# LED.net
KiCad netlist of a schematic drawn in Altium Designer
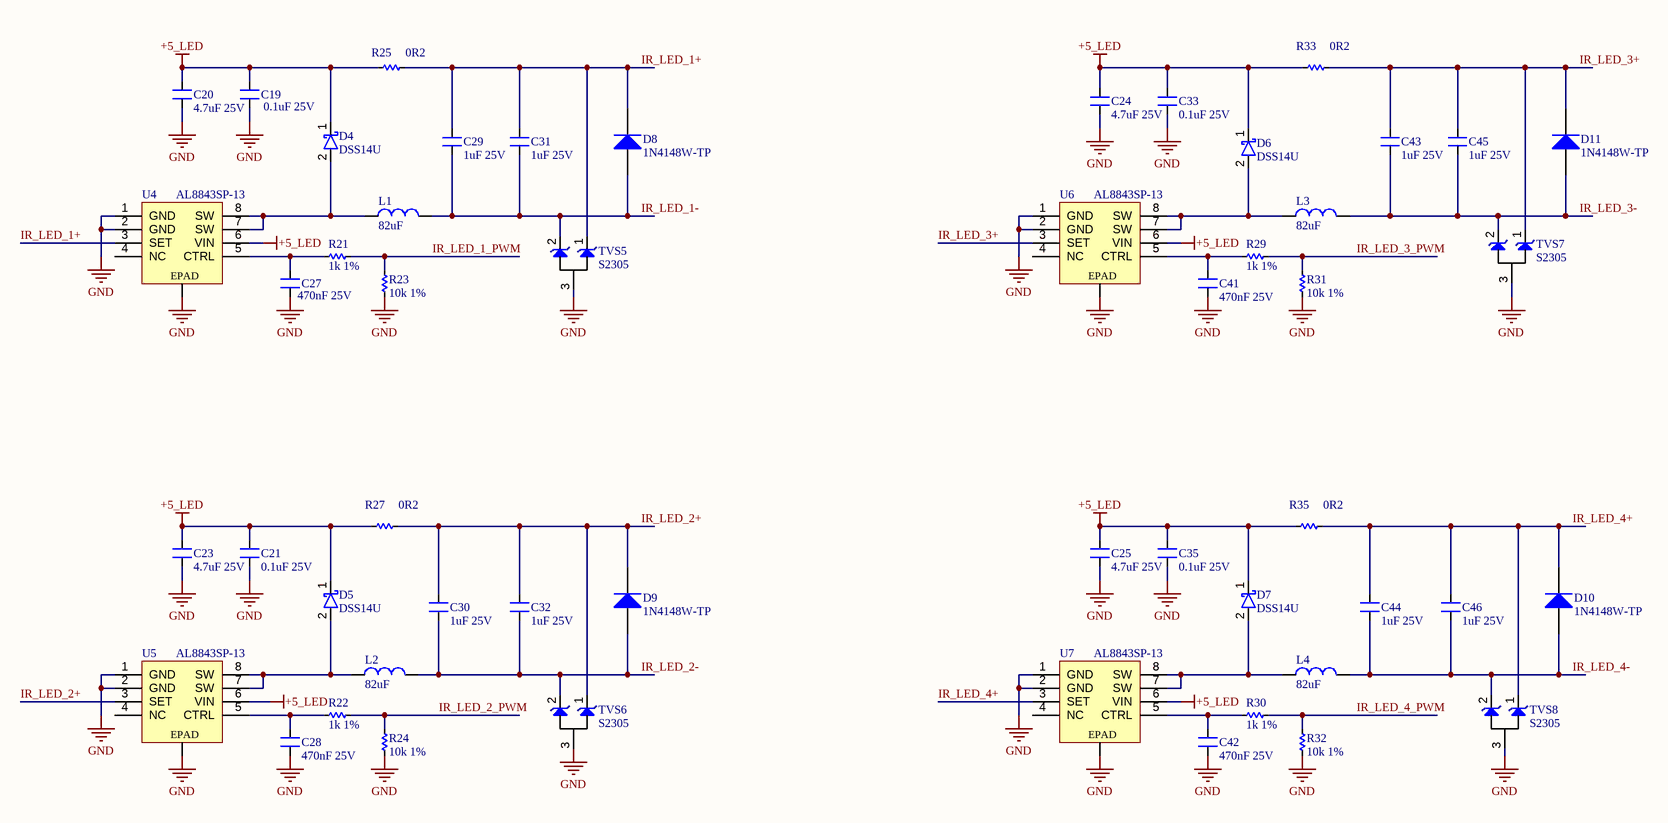
[diagram p0: LED.SchDoc]

(export (version "E")
  (design (tool "Eeschema 10.0.6"))
  (components
    (comp (ref "C19")
      (value "0.1uF 25V")
      (footprint "CN-SMD-0603")
      (libsource (lib "Sang_library") (part "Capacitors"))
    )
    (comp (ref "C20")
      (value "4.7uF 25V")
      (footprint "CN-SMD-0603")
      (libsource (lib "Sang_library") (part "Capacitors"))
    )
    (comp (ref "C21")
      (value "0.1uF 25V")
      (footprint "CN-SMD-0603")
      (libsource (lib "Sang_library") (part "Capacitors"))
    )
    (comp (ref "C23")
      (value "4.7uF 25V")
      (footprint "CN-SMD-0603")
      (libsource (lib "Sang_library") (part "Capacitors"))
    )
    (comp (ref "C24")
      (value "4.7uF 25V")
      (footprint "CN-SMD-0603")
      (libsource (lib "Sang_library") (part "Capacitors"))
    )
    (comp (ref "C25")
      (value "4.7uF 25V")
      (footprint "CN-SMD-0603")
      (libsource (lib "Sang_library") (part "Capacitors"))
    )
    (comp (ref "C27")
      (value "470nF 25V")
      (footprint "CN-SMD-0603")
      (libsource (lib "Sang_library") (part "Capacitors"))
    )
    (comp (ref "C28")
      (value "470nF 25V")
      (footprint "CN-SMD-0603")
      (libsource (lib "Sang_library") (part "Capacitors"))
    )
    (comp (ref "C29")
      (value "1uF 25V")
      (footprint "CN-SMD-0603")
      (libsource (lib "Sang_library") (part "Capacitors"))
    )
    (comp (ref "C30")
      (value "1uF 25V")
      (footprint "CN-SMD-0603")
      (libsource (lib "Sang_library") (part "Capacitors"))
    )
    (comp (ref "C31")
      (value "1uF 25V")
      (footprint "CN-SMD-0603")
      (libsource (lib "Sang_library") (part "Capacitors"))
    )
    (comp (ref "C32")
      (value "1uF 25V")
      (footprint "CN-SMD-0603")
      (libsource (lib "Sang_library") (part "Capacitors"))
    )
    (comp (ref "C33")
      (value "0.1uF 25V")
      (footprint "CN-SMD-0603")
      (libsource (lib "Sang_library") (part "Capacitors"))
    )
    (comp (ref "C35")
      (value "0.1uF 25V")
      (footprint "CN-SMD-0603")
      (libsource (lib "Sang_library") (part "Capacitors"))
    )
    (comp (ref "C41")
      (value "470nF 25V")
      (footprint "CN-SMD-0603")
      (libsource (lib "Sang_library") (part "Capacitors"))
    )
    (comp (ref "C42")
      (value "470nF 25V")
      (footprint "CN-SMD-0603")
      (libsource (lib "Sang_library") (part "Capacitors"))
    )
    (comp (ref "C43")
      (value "1uF 25V")
      (footprint "CN-SMD-0603")
      (libsource (lib "Sang_library") (part "Capacitors"))
    )
    (comp (ref "C44")
      (value "1uF 25V")
      (footprint "CN-SMD-0603")
      (libsource (lib "Sang_library") (part "Capacitors"))
    )
    (comp (ref "C45")
      (value "1uF 25V")
      (footprint "CN-SMD-0603")
      (libsource (lib "Sang_library") (part "Capacitors"))
    )
    (comp (ref "C46")
      (value "1uF 25V")
      (footprint "CN-SMD-0603")
      (libsource (lib "Sang_library") (part "Capacitors"))
    )
    (comp (ref "D4") (value "DSS14U") (footprint "sod-123") (libsource (lib "Sang_library") (part "DSS14U")))
    (comp (ref "D5") (value "DSS14U") (footprint "sod-123") (libsource (lib "Sang_library") (part "DSS14U")))
    (comp (ref "D6") (value "DSS14U") (footprint "sod-123") (libsource (lib "Sang_library") (part "DSS14U")))
    (comp (ref "D7") (value "DSS14U") (footprint "sod-123") (libsource (lib "Sang_library") (part "DSS14U")))
    (comp (ref "D8")
      (value "1N4148W-TP")
      (footprint "SOD-123")
      (description "DIODE GEN PURP 100V 300MA SOD123")
      (fields (field (name "MPN") "1N4148W-7-F") (field (name "MFR") "Diodes Incorporated"))
      (libsource (lib "Sang_library") (part "1N4148-W-7"))
    )
    (comp (ref "D9")
      (value "1N4148W-TP")
      (footprint "SOD-123")
      (description "DIODE GEN PURP 100V 300MA SOD123")
      (fields (field (name "MPN") "1N4148W-7-F") (field (name "MFR") "Diodes Incorporated"))
      (libsource (lib "Sang_library") (part "1N4148-W-7"))
    )
    (comp (ref "D10")
      (value "1N4148W-TP")
      (footprint "SOD-123")
      (description "DIODE GEN PURP 100V 300MA SOD123")
      (fields (field (name "MPN") "1N4148W-7-F") (field (name "MFR") "Diodes Incorporated"))
      (libsource (lib "Sang_library") (part "1N4148-W-7"))
    )
    (comp (ref "D11")
      (value "1N4148W-TP")
      (footprint "SOD-123")
      (description "DIODE GEN PURP 100V 300MA SOD123")
      (fields (field (name "MPN") "1N4148W-7-F") (field (name "MFR") "Diodes Incorporated"))
      (libsource (lib "Sang_library") (part "1N4148-W-7"))
    )
    (comp (ref "L1")
      (value "82uF")
      (footprint "L-SMD-M-4.8x4.8x2.8mm")
      (description "FIXED IND 82UH 2.25A 160MOHM SMD\r\nPN: 744770182")
      (fields
        (field (name "PARTNO") "78477010")
        (field (name "MANUFACTURER") "Wurth Elektronik")
        (field (name "CREATED BY") "Baojun Chen")
      )
      (libsource (lib "Sang_library") (part "L-SMD-1"))
    )
    (comp (ref "L2")
      (value "82uF")
      (footprint "L-SMD-M-4.8x4.8x2.8mm")
      (description "FIXED IND 82UH 2.25A 160MOHM SMD\r\nPN: 744770182")
      (fields
        (field (name "PARTNO") "78477010")
        (field (name "MANUFACTURER") "Wurth Elektronik")
        (field (name "CREATED BY") "Baojun Chen")
      )
      (libsource (lib "Sang_library") (part "L-SMD-1"))
    )
    (comp (ref "L3")
      (value "82uF")
      (footprint "L-SMD-M-4.8x4.8x2.8mm")
      (description "FIXED IND 82UH 2.25A 160MOHM SMD\r\nPN: 744770182")
      (fields
        (field (name "PARTNO") "78477010")
        (field (name "MANUFACTURER") "Wurth Elektronik")
        (field (name "CREATED BY") "Baojun Chen")
      )
      (libsource (lib "Sang_library") (part "L-SMD-1"))
    )
    (comp (ref "L4")
      (value "82uF")
      (footprint "L-SMD-M-4.8x4.8x2.8mm")
      (description "FIXED IND 82UH 2.25A 160MOHM SMD\r\nPN: 744770182")
      (fields
        (field (name "PARTNO") "78477010")
        (field (name "MANUFACTURER") "Wurth Elektronik")
        (field (name "CREATED BY") "Baojun Chen")
      )
      (libsource (lib "Sang_library") (part "L-SMD-1"))
    )
    (comp (ref "R21")
      (value "1k 1%")
      (footprint "RES-SMD-0603")
      (description "SMD")
      (fields
        (field (name "MANUFACTURER") "Generic Components")
        (field (name "PUBLISHER") "Altium Hobart Technology Centre")
      )
      (libsource (lib "Sang_library") (part "Res SMD"))
    )
    (comp (ref "R22")
      (value "1k 1%")
      (footprint "RES-SMD-0603")
      (description "SMD")
      (fields
        (field (name "MANUFACTURER") "Generic Components")
        (field (name "PUBLISHER") "Altium Hobart Technology Centre")
      )
      (libsource (lib "Sang_library") (part "Res SMD"))
    )
    (comp (ref "R23")
      (value "10k 1%")
      (footprint "RES-SMD-0603")
      (description "SMD")
      (fields
        (field (name "MANUFACTURER") "Generic Components")
        (field (name "PUBLISHER") "Altium Hobart Technology Centre")
      )
      (libsource (lib "Sang_library") (part "Res SMD"))
    )
    (comp (ref "R24")
      (value "10k 1%")
      (footprint "RES-SMD-0603")
      (description "SMD")
      (fields
        (field (name "MANUFACTURER") "Generic Components")
        (field (name "PUBLISHER") "Altium Hobart Technology Centre")
      )
      (libsource (lib "Sang_library") (part "Res SMD"))
    )
    (comp (ref "R25")
      (value "0R2")
      (footprint "RES-SMD-1206")
      (description "RES 0.1 OHM 1% 1W 1206\r\nPN: PE1206FRF470R1L")
      (fields
        (field (name "MANUFACTURER") "Generic Components")
        (field (name "PUBLISHER") "Altium Hobart Technology Centre")
      )
      (libsource (lib "Library") (part "Res-SMD"))
    )
    (comp (ref "R27")
      (value "0R2")
      (footprint "RES-SMD-1206")
      (description "RES 0.1 OHM 1% 1W 1206\r\nPN: PE1206FRF470R1L")
      (fields
        (field (name "MANUFACTURER") "Generic Components")
        (field (name "PUBLISHER") "Altium Hobart Technology Centre")
      )
      (libsource (lib "Library") (part "Res-SMD"))
    )
    (comp (ref "R29")
      (value "1k 1%")
      (footprint "RES-SMD-0603")
      (description "SMD")
      (fields
        (field (name "MANUFACTURER") "Generic Components")
        (field (name "PUBLISHER") "Altium Hobart Technology Centre")
      )
      (libsource (lib "Sang_library") (part "Res SMD"))
    )
    (comp (ref "R30")
      (value "1k 1%")
      (footprint "RES-SMD-0603")
      (description "SMD")
      (fields
        (field (name "MANUFACTURER") "Generic Components")
        (field (name "PUBLISHER") "Altium Hobart Technology Centre")
      )
      (libsource (lib "Sang_library") (part "Res SMD"))
    )
    (comp (ref "R31")
      (value "10k 1%")
      (footprint "RES-SMD-0603")
      (description "SMD")
      (fields
        (field (name "MANUFACTURER") "Generic Components")
        (field (name "PUBLISHER") "Altium Hobart Technology Centre")
      )
      (libsource (lib "Sang_library") (part "Res SMD"))
    )
    (comp (ref "R32")
      (value "10k 1%")
      (footprint "RES-SMD-0603")
      (description "SMD")
      (fields
        (field (name "MANUFACTURER") "Generic Components")
        (field (name "PUBLISHER") "Altium Hobart Technology Centre")
      )
      (libsource (lib "Sang_library") (part "Res SMD"))
    )
    (comp (ref "R33")
      (value "0R2")
      (footprint "RES-SMD-1206")
      (description "RES 0.1 OHM 1% 1W 1206\r\nPN: PE1206FRF470R1L")
      (fields
        (field (name "MANUFACTURER") "Generic Components")
        (field (name "PUBLISHER") "Altium Hobart Technology Centre")
      )
      (libsource (lib "Library") (part "Res-SMD"))
    )
    (comp (ref "R35")
      (value "0R2")
      (footprint "RES-SMD-1206")
      (description "RES 0.1 OHM 1% 1W 1206\r\nPN: PE1206FRF470R1L")
      (fields
        (field (name "MANUFACTURER") "Generic Components")
        (field (name "PUBLISHER") "Altium Hobart Technology Centre")
      )
      (libsource (lib "Library") (part "Res-SMD"))
    )
    (comp (ref "TVS5")
      (value "S2305")
      (footprint "sot23-12_3")
      (description "TVS DIODE 5VWM 10.8VC SOT23")
      (libsource (lib "Sang_library") (part "S2305"))
    )
    (comp (ref "TVS6")
      (value "S2305")
      (footprint "sot23-12_3")
      (description "TVS DIODE 5VWM 10.8VC SOT23")
      (libsource (lib "Sang_library") (part "S2305"))
    )
    (comp (ref "TVS7")
      (value "S2305")
      (footprint "sot23-12_3")
      (description "TVS DIODE 5VWM 10.8VC SOT23")
      (libsource (lib "Sang_library") (part "S2305"))
    )
    (comp (ref "TVS8")
      (value "S2305")
      (footprint "sot23-12_3")
      (description "TVS DIODE 5VWM 10.8VC SOT23")
      (libsource (lib "Sang_library") (part "S2305"))
    )
    (comp (ref "U4")
      (value "AL8843SP-13")
      (footprint "SO8_EPAD")
      (description "IC LED DRIVER RGLTR PWM 3A 8SO")
      (libsource (lib "Sang_library") (part "AL8843SP-13"))
    )
    (comp (ref "U5")
      (value "AL8843SP-13")
      (footprint "SO8_EPAD")
      (description "IC LED DRIVER RGLTR PWM 3A 8SO")
      (libsource (lib "Sang_library") (part "AL8843SP-13"))
    )
    (comp (ref "U6")
      (value "AL8843SP-13")
      (footprint "SO8_EPAD")
      (description "IC LED DRIVER RGLTR PWM 3A 8SO")
      (libsource (lib "Sang_library") (part "AL8843SP-13"))
    )
    (comp (ref "U7")
      (value "AL8843SP-13")
      (footprint "SO8_EPAD")
      (description "IC LED DRIVER RGLTR PWM 3A 8SO")
      (libsource (lib "Sang_library") (part "AL8843SP-13"))
    )
  )
  (nets
    (net (code "1") (name "+5_LED") (class "Default")
      (node (ref "C19") (pin "2") (pinfunction "2_2") (pintype "passive"))
      (node (ref "C20") (pin "2") (pinfunction "2_2") (pintype "passive"))
      (node (ref "C21") (pin "2") (pinfunction "2_2") (pintype "passive"))
      (node (ref "C23") (pin "2") (pinfunction "2_2") (pintype "passive"))
      (node (ref "C24") (pin "2") (pinfunction "2_2") (pintype "passive"))
      (node (ref "C25") (pin "2") (pinfunction "2_2") (pintype "passive"))
      (node (ref "C33") (pin "2") (pinfunction "2_2") (pintype "passive"))
      (node (ref "C35") (pin "2") (pinfunction "2_2") (pintype "passive"))
      (node (ref "D4") (pin "1") (pinfunction "1_1") (pintype "passive"))
      (node (ref "D5") (pin "1") (pinfunction "1_1") (pintype "passive"))
      (node (ref "D6") (pin "1") (pinfunction "1_1") (pintype "passive"))
      (node (ref "D7") (pin "1") (pinfunction "1_1") (pintype "passive"))
      (node (ref "R25") (pin "2") (pinfunction "2_2") (pintype "passive"))
      (node (ref "R27") (pin "2") (pinfunction "2_2") (pintype "passive"))
      (node (ref "R33") (pin "2") (pinfunction "2_2") (pintype "passive"))
      (node (ref "R35") (pin "2") (pinfunction "2_2") (pintype "passive"))
      (node (ref "U4") (pin "6") (pinfunction "VIN_6") (pintype "passive"))
      (node (ref "U5") (pin "6") (pinfunction "VIN_6") (pintype "passive"))
      (node (ref "U6") (pin "6") (pinfunction "VIN_6") (pintype "passive"))
      (node (ref "U7") (pin "6") (pinfunction "VIN_6") (pintype "passive"))
    )
    (net (code "2") (name "/IR_LED_1+") (class "Default")
      (node (ref "C29") (pin "2") (pinfunction "2_2") (pintype "passive"))
      (node (ref "C31") (pin "2") (pinfunction "2_2") (pintype "passive"))
      (node (ref "D8") (pin "2") (pinfunction "K_2") (pintype "passive"))
      (node (ref "R25") (pin "1") (pinfunction "1_1") (pintype "passive"))
      (node (ref "TVS5") (pin "1") (pinfunction "1_1") (pintype "passive"))
      (node (ref "U4") (pin "3") (pinfunction "SET_3") (pintype "passive"))
    )
    (net (code "3") (name "/IR_LED_1-") (class "Default")
      (node (ref "C29") (pin "1") (pinfunction "1_1") (pintype "passive"))
      (node (ref "C31") (pin "1") (pinfunction "1_1") (pintype "passive"))
      (node (ref "D8") (pin "1") (pinfunction "A_1") (pintype "passive"))
      (node (ref "L1") (pin "2") (pinfunction "2_2") (pintype "passive"))
      (node (ref "TVS5") (pin "2") (pinfunction "2_2") (pintype "passive"))
    )
    (net (code "4") (name "/IR_LED_1_PWM") (class "Default")
      (node (ref "R21") (pin "2") (pinfunction "2_2") (pintype "passive"))
      (node (ref "R23") (pin "2") (pinfunction "2_2") (pintype "passive"))
    )
    (net (code "5") (name "/IR_LED_2+") (class "Default")
      (node (ref "C30") (pin "2") (pinfunction "2_2") (pintype "passive"))
      (node (ref "C32") (pin "2") (pinfunction "2_2") (pintype "passive"))
      (node (ref "D9") (pin "2") (pinfunction "K_2") (pintype "passive"))
      (node (ref "R27") (pin "1") (pinfunction "1_1") (pintype "passive"))
      (node (ref "TVS6") (pin "1") (pinfunction "1_1") (pintype "passive"))
      (node (ref "U5") (pin "3") (pinfunction "SET_3") (pintype "passive"))
    )
    (net (code "6") (name "/IR_LED_2-") (class "Default")
      (node (ref "C30") (pin "1") (pinfunction "1_1") (pintype "passive"))
      (node (ref "C32") (pin "1") (pinfunction "1_1") (pintype "passive"))
      (node (ref "D9") (pin "1") (pinfunction "A_1") (pintype "passive"))
      (node (ref "L2") (pin "2") (pinfunction "2_2") (pintype "passive"))
      (node (ref "TVS6") (pin "2") (pinfunction "2_2") (pintype "passive"))
    )
    (net (code "7") (name "/IR_LED_2_PWM") (class "Default")
      (node (ref "R22") (pin "2") (pinfunction "2_2") (pintype "passive"))
      (node (ref "R24") (pin "2") (pinfunction "2_2") (pintype "passive"))
    )
    (net (code "8") (name "/IR_LED_3+") (class "Default")
      (node (ref "C43") (pin "2") (pinfunction "2_2") (pintype "passive"))
      (node (ref "C45") (pin "2") (pinfunction "2_2") (pintype "passive"))
      (node (ref "D11") (pin "2") (pinfunction "K_2") (pintype "passive"))
      (node (ref "R33") (pin "1") (pinfunction "1_1") (pintype "passive"))
      (node (ref "TVS7") (pin "1") (pinfunction "1_1") (pintype "passive"))
      (node (ref "U6") (pin "3") (pinfunction "SET_3") (pintype "passive"))
    )
    (net (code "9") (name "/IR_LED_3-") (class "Default")
      (node (ref "C43") (pin "1") (pinfunction "1_1") (pintype "passive"))
      (node (ref "C45") (pin "1") (pinfunction "1_1") (pintype "passive"))
      (node (ref "D11") (pin "1") (pinfunction "A_1") (pintype "passive"))
      (node (ref "L3") (pin "2") (pinfunction "2_2") (pintype "passive"))
      (node (ref "TVS7") (pin "2") (pinfunction "2_2") (pintype "passive"))
    )
    (net (code "10") (name "/IR_LED_3_PWM") (class "Default")
      (node (ref "R29") (pin "2") (pinfunction "2_2") (pintype "passive"))
      (node (ref "R31") (pin "2") (pinfunction "2_2") (pintype "passive"))
    )
    (net (code "11") (name "/IR_LED_4+") (class "Default")
      (node (ref "C44") (pin "2") (pinfunction "2_2") (pintype "passive"))
      (node (ref "C46") (pin "2") (pinfunction "2_2") (pintype "passive"))
      (node (ref "D10") (pin "2") (pinfunction "K_2") (pintype "passive"))
      (node (ref "R35") (pin "1") (pinfunction "1_1") (pintype "passive"))
      (node (ref "TVS8") (pin "1") (pinfunction "1_1") (pintype "passive"))
      (node (ref "U7") (pin "3") (pinfunction "SET_3") (pintype "passive"))
    )
    (net (code "12") (name "/IR_LED_4-") (class "Default")
      (node (ref "C44") (pin "1") (pinfunction "1_1") (pintype "passive"))
      (node (ref "C46") (pin "1") (pinfunction "1_1") (pintype "passive"))
      (node (ref "D10") (pin "1") (pinfunction "A_1") (pintype "passive"))
      (node (ref "L4") (pin "2") (pinfunction "2_2") (pintype "passive"))
      (node (ref "TVS8") (pin "2") (pinfunction "2_2") (pintype "passive"))
    )
    (net (code "13") (name "/IR_LED_4_PWM") (class "Default")
      (node (ref "R30") (pin "2") (pinfunction "2_2") (pintype "passive"))
      (node (ref "R32") (pin "2") (pinfunction "2_2") (pintype "passive"))
    )
    (net (code "14") (name "GND") (class "Default")
      (node (ref "C19") (pin "1") (pinfunction "1_1") (pintype "passive"))
      (node (ref "C20") (pin "1") (pinfunction "1_1") (pintype "passive"))
      (node (ref "C21") (pin "1") (pinfunction "1_1") (pintype "passive"))
      (node (ref "C23") (pin "1") (pinfunction "1_1") (pintype "passive"))
      (node (ref "C24") (pin "1") (pinfunction "1_1") (pintype "passive"))
      (node (ref "C25") (pin "1") (pinfunction "1_1") (pintype "passive"))
      (node (ref "C27") (pin "1") (pinfunction "1_1") (pintype "passive"))
      (node (ref "C28") (pin "1") (pinfunction "1_1") (pintype "passive"))
      (node (ref "C33") (pin "1") (pinfunction "1_1") (pintype "passive"))
      (node (ref "C35") (pin "1") (pinfunction "1_1") (pintype "passive"))
      (node (ref "C41") (pin "1") (pinfunction "1_1") (pintype "passive"))
      (node (ref "C42") (pin "1") (pinfunction "1_1") (pintype "passive"))
      (node (ref "R23") (pin "1") (pinfunction "1_1") (pintype "passive"))
      (node (ref "R24") (pin "1") (pinfunction "1_1") (pintype "passive"))
      (node (ref "R31") (pin "1") (pinfunction "1_1") (pintype "passive"))
      (node (ref "R32") (pin "1") (pinfunction "1_1") (pintype "passive"))
      (node (ref "TVS5") (pin "3") (pinfunction "3_3") (pintype "passive"))
      (node (ref "TVS6") (pin "3") (pinfunction "3_3") (pintype "passive"))
      (node (ref "TVS7") (pin "3") (pinfunction "3_3") (pintype "passive"))
      (node (ref "TVS8") (pin "3") (pinfunction "3_3") (pintype "passive"))
      (node (ref "U4") (pin "1") (pinfunction "GND_1") (pintype "passive"))
      (node (ref "U4") (pin "2") (pinfunction "GND_2") (pintype "passive"))
      (node (ref "U4") (pin "EPAD") (pinfunction "EPAD_EPAD") (pintype "passive"))
      (node (ref "U5") (pin "1") (pinfunction "GND_1") (pintype "passive"))
      (node (ref "U5") (pin "2") (pinfunction "GND_2") (pintype "passive"))
      (node (ref "U5") (pin "EPAD") (pinfunction "EPAD_EPAD") (pintype "passive"))
      (node (ref "U6") (pin "1") (pinfunction "GND_1") (pintype "passive"))
      (node (ref "U6") (pin "2") (pinfunction "GND_2") (pintype "passive"))
      (node (ref "U6") (pin "EPAD") (pinfunction "EPAD_EPAD") (pintype "passive"))
      (node (ref "U7") (pin "1") (pinfunction "GND_1") (pintype "passive"))
      (node (ref "U7") (pin "2") (pinfunction "GND_2") (pintype "passive"))
      (node (ref "U7") (pin "EPAD") (pinfunction "EPAD_EPAD") (pintype "passive"))
    )
    (net (code "15") (name "Net-(D4-Pad2)") (class "Default")
      (node (ref "D4") (pin "2") (pinfunction "2_2") (pintype "passive"))
      (node (ref "L1") (pin "1") (pinfunction "1_1") (pintype "passive"))
      (node (ref "U4") (pin "7") (pinfunction "SW_7") (pintype "passive"))
      (node (ref "U4") (pin "8") (pinfunction "SW_8") (pintype "passive"))
    )
    (net (code "16") (name "Net-(D5-Pad2)") (class "Default")
      (node (ref "D5") (pin "2") (pinfunction "2_2") (pintype "passive"))
      (node (ref "L2") (pin "1") (pinfunction "1_1") (pintype "passive"))
      (node (ref "U5") (pin "7") (pinfunction "SW_7") (pintype "passive"))
      (node (ref "U5") (pin "8") (pinfunction "SW_8") (pintype "passive"))
    )
    (net (code "17") (name "Net-(D6-Pad2)") (class "Default")
      (node (ref "D6") (pin "2") (pinfunction "2_2") (pintype "passive"))
      (node (ref "L3") (pin "1") (pinfunction "1_1") (pintype "passive"))
      (node (ref "U6") (pin "7") (pinfunction "SW_7") (pintype "passive"))
      (node (ref "U6") (pin "8") (pinfunction "SW_8") (pintype "passive"))
    )
    (net (code "18") (name "Net-(D7-Pad2)") (class "Default")
      (node (ref "D7") (pin "2") (pinfunction "2_2") (pintype "passive"))
      (node (ref "L4") (pin "1") (pinfunction "1_1") (pintype "passive"))
      (node (ref "U7") (pin "7") (pinfunction "SW_7") (pintype "passive"))
      (node (ref "U7") (pin "8") (pinfunction "SW_8") (pintype "passive"))
    )
    (net (code "19") (name "Net-(U4-CTRL)") (class "Default")
      (node (ref "C27") (pin "2") (pinfunction "2_2") (pintype "passive"))
      (node (ref "R21") (pin "1") (pinfunction "1_1") (pintype "passive"))
      (node (ref "U4") (pin "5") (pinfunction "CTRL_5") (pintype "passive"))
    )
    (net (code "20") (name "Net-(U5-CTRL)") (class "Default")
      (node (ref "C28") (pin "2") (pinfunction "2_2") (pintype "passive"))
      (node (ref "R22") (pin "1") (pinfunction "1_1") (pintype "passive"))
      (node (ref "U5") (pin "5") (pinfunction "CTRL_5") (pintype "passive"))
    )
    (net (code "21") (name "Net-(U6-CTRL)") (class "Default")
      (node (ref "C41") (pin "2") (pinfunction "2_2") (pintype "passive"))
      (node (ref "R29") (pin "1") (pinfunction "1_1") (pintype "passive"))
      (node (ref "U6") (pin "5") (pinfunction "CTRL_5") (pintype "passive"))
    )
    (net (code "22") (name "Net-(U7-CTRL)") (class "Default")
      (node (ref "C42") (pin "2") (pinfunction "2_2") (pintype "passive"))
      (node (ref "R30") (pin "1") (pinfunction "1_1") (pintype "passive"))
      (node (ref "U7") (pin "5") (pinfunction "CTRL_5") (pintype "passive"))
    )
    (net (code "23") (name "unconnected-(U4-NC-Pad4)") (class "Default")
      (node (ref "U4") (pin "4") (pinfunction "NC_4") (pintype "passive"))
    )
    (net (code "24") (name "unconnected-(U5-NC-Pad4)") (class "Default")
      (node (ref "U5") (pin "4") (pinfunction "NC_4") (pintype "passive"))
    )
    (net (code "25") (name "unconnected-(U6-NC-Pad4)") (class "Default")
      (node (ref "U6") (pin "4") (pinfunction "NC_4") (pintype "passive"))
    )
    (net (code "26") (name "unconnected-(U7-NC-Pad4)") (class "Default")
      (node (ref "U7") (pin "4") (pinfunction "NC_4") (pintype "passive"))
    )
  )
)
